# PowerBoard.net
KiCad netlist of a schematic drawn in Altium Designer
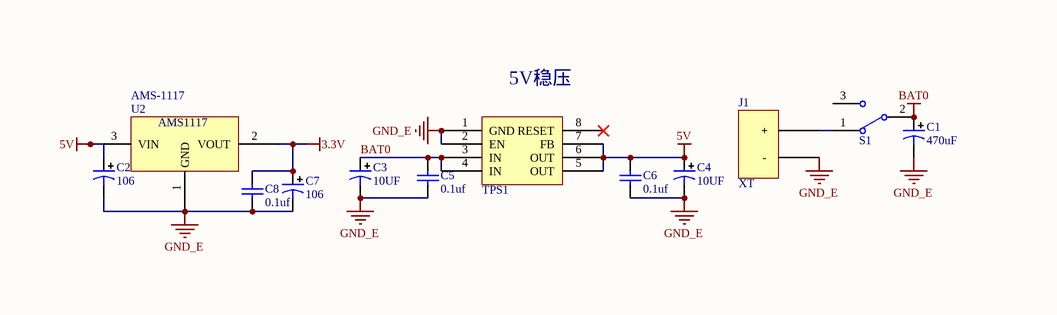
[diagram p0: PowerBoard.SchDoc, top left]
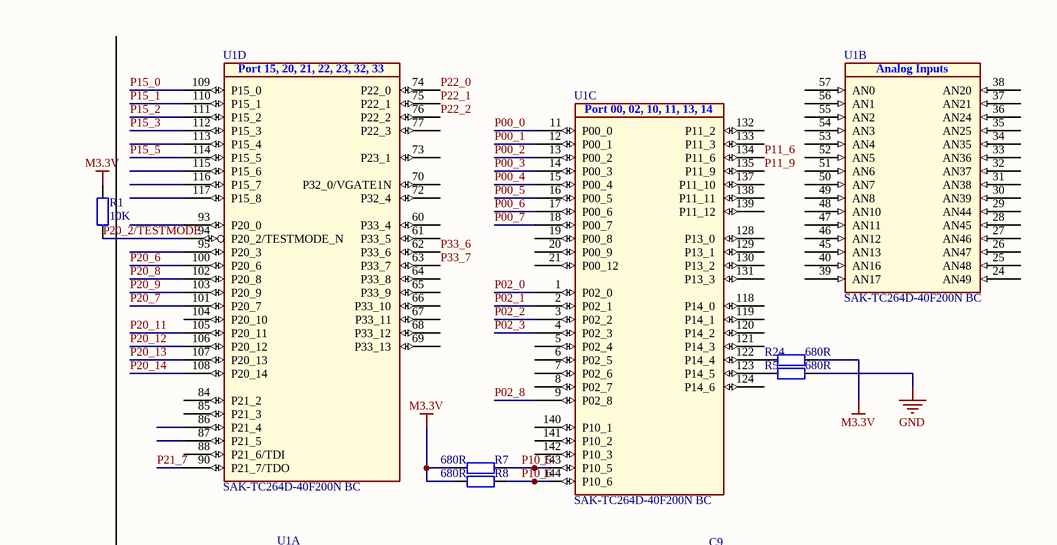
[diagram p1: PowerBoard.SchDoc, top right]
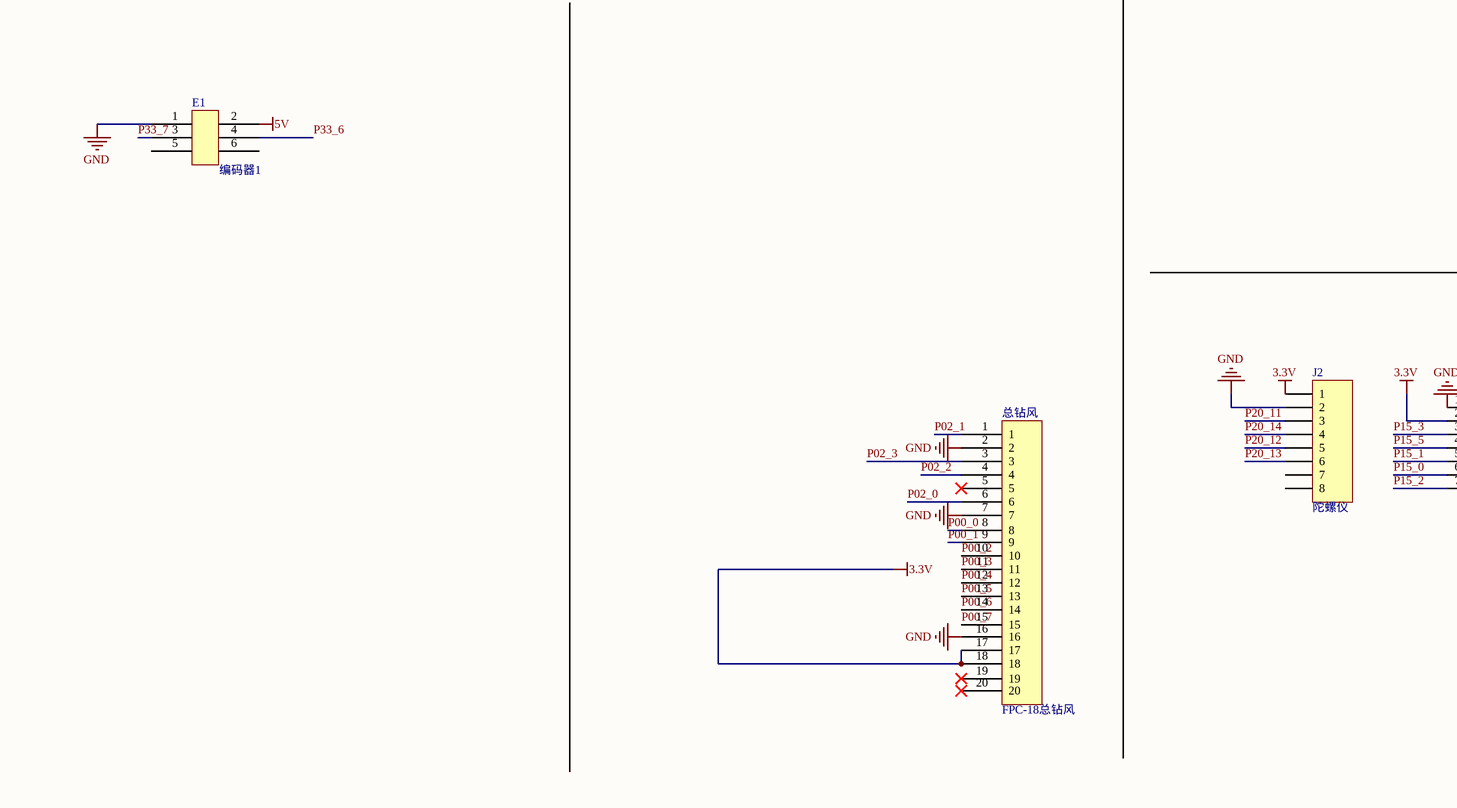
[diagram p2: PowerBoard.SchDoc, bottom left]
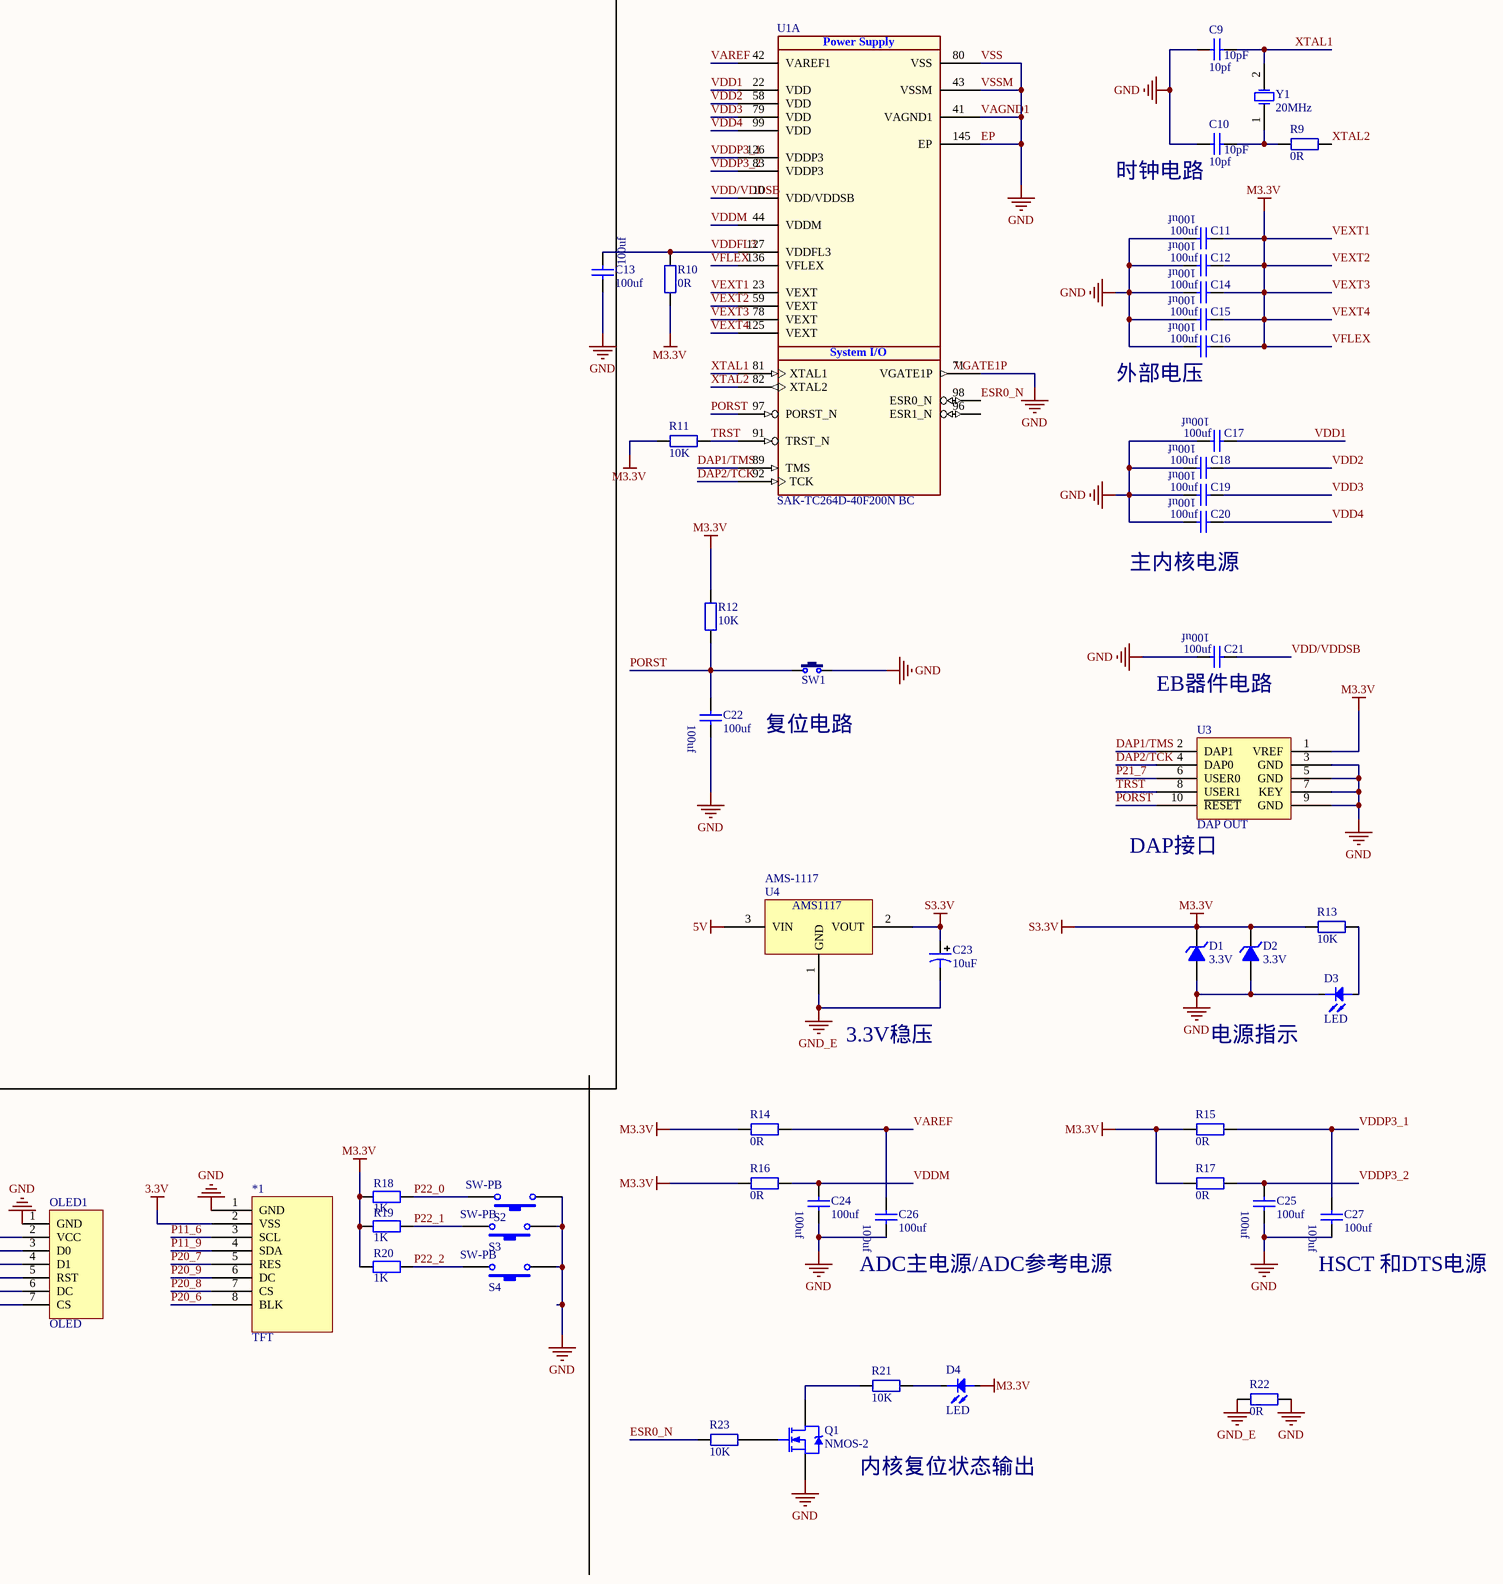
[diagram p3: PowerBoard.SchDoc, bottom right]

(export (version "E")
  (design (tool "Eeschema 10.0.6"))
  (components
    (comp (ref "*1") (value "TFT") (footprint "1.8TFT彩屏") (libsource (lib "PowerBoard") (part "TFT")))
    (comp (ref "C1")
      (value "470uF")
      (footprint "CM E(8*10.2)")
      (description "Capacitor")
      (fields (field (name "Comment") "470uf") (field (name "PUBLISHER") "Altium Limited"))
      (libsource (lib "PowerBoard") (part "Cap2"))
    )
    (comp (ref "C2")
      (value "106")
      (footprint "1206")
      (description "Capacitor")
      (fields (field (name "Comment") "10uf") (field (name "PUBLISHER") "Altium Limited"))
      (libsource (lib "主板常用元器件") (part "Cap2"))
    )
    (comp (ref "C3")
      (value "10UF")
      (footprint "1206")
      (description "Capacitor")
      (fields (field (name "Comment") "10uf") (field (name "PUBLISHER") "Altium Limited"))
      (libsource (lib "主板常用元器件") (part "Cap2"))
    )
    (comp (ref "C4")
      (value "10UF")
      (footprint "1206")
      (description "Capacitor")
      (fields (field (name "Comment") "10uf") (field (name "PUBLISHER") "Altium Limited"))
      (libsource (lib "主板常用元器件") (part "Cap2"))
    )
    (comp (ref "C5")
      (value "0.1uf")
      (footprint "0805C")
      (description "Capacitor")
      (fields (field (name "PUBLISHER") "Altium Limited"))
      (libsource (lib "PowerBoard") (part "Cap1"))
    )
    (comp (ref "C6")
      (value "0.1uf")
      (footprint "0805C")
      (description "Capacitor")
      (fields (field (name "PUBLISHER") "Altium Limited"))
      (libsource (lib "PowerBoard") (part "Cap1"))
    )
    (comp (ref "C7")
      (value "106")
      (footprint "1206")
      (description "Capacitor")
      (fields (field (name "Comment") "10uf") (field (name "PUBLISHER") "Altium Limited"))
      (libsource (lib "主板常用元器件") (part "Cap2"))
    )
    (comp (ref "C8")
      (value "0.1uf")
      (footprint "0805C")
      (description "Capacitor")
      (fields (field (name "PUBLISHER") "Altium Limited"))
      (libsource (lib "PowerBoard") (part "Cap1"))
    )
    (comp (ref "C9")
      (value "10pf")
      (footprint "0805C")
      (description "Capacitor")
      (fields (field (name "PUBLISHER") "Altium Limited"))
      (libsource (lib "PowerBoard") (part "Cap_1"))
    )
    (comp (ref "C10")
      (value "10pf")
      (footprint "0805C")
      (description "Capacitor")
      (fields (field (name "PUBLISHER") "Altium Limited"))
      (libsource (lib "PowerBoard") (part "Cap_1"))
    )
    (comp (ref "C11")
      (value "100uf")
      (footprint "0805C")
      (description "Capacitor")
      (fields (field (name "PUBLISHER") "Altium Limited"))
      (libsource (lib "PowerBoard") (part "Cap"))
    )
    (comp (ref "C12")
      (value "100uf")
      (footprint "0805C")
      (description "Capacitor")
      (fields (field (name "PUBLISHER") "Altium Limited"))
      (libsource (lib "PowerBoard") (part "Cap"))
    )
    (comp (ref "C13")
      (value "100uf")
      (footprint "0805C")
      (description "Capacitor")
      (fields (field (name "PUBLISHER") "Altium Limited"))
      (libsource (lib "PowerBoard") (part "Cap"))
    )
    (comp (ref "C14")
      (value "100uf")
      (footprint "0805C")
      (description "Capacitor")
      (fields (field (name "PUBLISHER") "Altium Limited"))
      (libsource (lib "PowerBoard") (part "Cap"))
    )
    (comp (ref "C15")
      (value "100uf")
      (footprint "0805C")
      (description "Capacitor")
      (fields (field (name "PUBLISHER") "Altium Limited"))
      (libsource (lib "PowerBoard") (part "Cap"))
    )
    (comp (ref "C16")
      (value "100uf")
      (footprint "0805C")
      (description "Capacitor")
      (fields (field (name "PUBLISHER") "Altium Limited"))
      (libsource (lib "PowerBoard") (part "Cap"))
    )
    (comp (ref "C17")
      (value "100uf")
      (footprint "0805C")
      (description "Capacitor")
      (fields (field (name "PUBLISHER") "Altium Limited"))
      (libsource (lib "PowerBoard") (part "Cap"))
    )
    (comp (ref "C18")
      (value "100uf")
      (footprint "0805C")
      (description "Capacitor")
      (fields (field (name "PUBLISHER") "Altium Limited"))
      (libsource (lib "PowerBoard") (part "Cap"))
    )
    (comp (ref "C19")
      (value "100uf")
      (footprint "0805C")
      (description "Capacitor")
      (fields (field (name "PUBLISHER") "Altium Limited"))
      (libsource (lib "PowerBoard") (part "Cap"))
    )
    (comp (ref "C20")
      (value "100uf")
      (footprint "0805C")
      (description "Capacitor")
      (fields (field (name "PUBLISHER") "Altium Limited"))
      (libsource (lib "PowerBoard") (part "Cap"))
    )
    (comp (ref "C21")
      (value "100uf")
      (footprint "0805C")
      (description "Capacitor")
      (fields (field (name "PUBLISHER") "Altium Limited"))
      (libsource (lib "PowerBoard") (part "Cap"))
    )
    (comp (ref "C22")
      (value "100uf")
      (footprint "0805C")
      (description "Capacitor")
      (fields (field (name "PUBLISHER") "Altium Limited"))
      (libsource (lib "PowerBoard") (part "Cap"))
    )
    (comp (ref "C23")
      (value "10uF")
      (footprint "CM E(8*10.2)")
      (description "Capacitor")
      (fields (field (name "Comment") "10uf") (field (name "PUBLISHER") "Altium Limited"))
      (libsource (lib "PowerBoard") (part "Cap2_1"))
    )
    (comp (ref "C24")
      (value "100uf")
      (footprint "0805C")
      (description "Capacitor")
      (fields (field (name "PUBLISHER") "Altium Limited"))
      (libsource (lib "PowerBoard") (part "Cap"))
    )
    (comp (ref "C25")
      (value "100uf")
      (footprint "0805C")
      (description "Capacitor")
      (fields (field (name "PUBLISHER") "Altium Limited"))
      (libsource (lib "PowerBoard") (part "Cap"))
    )
    (comp (ref "C26")
      (value "100uf")
      (footprint "0805C")
      (description "Capacitor")
      (fields (field (name "PUBLISHER") "Altium Limited"))
      (libsource (lib "PowerBoard") (part "Cap"))
    )
    (comp (ref "C27")
      (value "100uf")
      (footprint "0805C")
      (description "Capacitor")
      (fields (field (name "PUBLISHER") "Altium Limited"))
      (libsource (lib "PowerBoard") (part "Cap"))
    )
    (comp (ref "D1")
      (value "3.3V")
      (footprint "DO-35")
      (fields (field (name "版权归属") "源创客"))
      (libsource (lib "PowerBoard") (part "DIODE"))
    )
    (comp (ref "D2")
      (value "3.3V")
      (footprint "DO-35")
      (fields (field (name "版权归属") "源创客"))
      (libsource (lib "PowerBoard") (part "DIODE"))
    )
    (comp (ref "D3") (value "LED") (footprint "0805LED") (libsource (lib "PowerBoard") (part "LED")))
    (comp (ref "D4") (value "LED") (footprint "0805LED") (libsource (lib "PowerBoard") (part "LED")))
    (comp (ref "E1") (value "编码器1") (footprint "IDC-6") (libsource (lib "主板常用元器件") (part "DIP6")))
    (comp (ref "J1") (value "XT") (footprint "XT60") (libsource (lib "PowerBoard") (part "XT")))
    (comp (ref "J2")
      (value "陀螺仪")
      (footprint "HDR1X8")
      (description "Header, 8-Pin")
      (fields (field (name "PUBLISHER") "Altium Limited"))
      (libsource (lib "4.5   - 接插件-脚距2.54") (part "Header 8"))
    )
    (comp (ref "OLED1")
      (value "OLED")
      (footprint "SIP7")
      (fields (field (name "版权归属") "源创客"))
      (libsource (lib "PowerBoard") (part "OLED 1.3-12864_7pin"))
    )
    (comp (ref "Q1")
      (value "NMOS-2")
      (footprint "SOT23-3")
      (description "N-Channel Power MOSFET")
      (fields (field (name "PUBLISHER") "Altium Limited"))
      (libsource (lib "Miscellaneous Devices") (part "NMOS-2"))
    )
    (comp (ref "R1") (value "10K") (footprint "0805R") (libsource (lib "PowerBoard") (part "RES_3")))
    (comp (ref "R5") (value "680R") (footprint "0805R") (libsource (lib "PowerBoard") (part "RES")))
    (comp (ref "R7") (value "680R") (footprint "0805R") (libsource (lib "PowerBoard") (part "RES")))
    (comp (ref "R8") (value "680R") (footprint "0805R") (libsource (lib "PowerBoard") (part "RES")))
    (comp (ref "R9") (value "0R") (footprint "0805R") (libsource (lib "PowerBoard") (part "RES_2")))
    (comp (ref "R10") (value "0R") (footprint "0805R") (libsource (lib "PowerBoard") (part "RES_2")))
    (comp (ref "R11") (value "10K") (footprint "0805R") (libsource (lib "PowerBoard") (part "RES_3")))
    (comp (ref "R12") (value "10K") (footprint "0805R") (libsource (lib "PowerBoard") (part "RES_3")))
    (comp (ref "R13") (value "10K") (footprint "0805R") (libsource (lib "PowerBoard") (part "RES_3")))
    (comp (ref "R14") (value "0R") (footprint "0805R") (libsource (lib "PowerBoard") (part "RES_2")))
    (comp (ref "R15") (value "0R") (footprint "0805R") (libsource (lib "PowerBoard") (part "RES_2")))
    (comp (ref "R16") (value "0R") (footprint "0805R") (libsource (lib "PowerBoard") (part "RES_2")))
    (comp (ref "R17") (value "0R") (footprint "0805R") (libsource (lib "PowerBoard") (part "RES_2")))
    (comp (ref "R18")
      (value "1K")
      (footprint "0805R")
      (description "Resistor")
      (fields (field (name "Comment") "Res2") (field (name "PUBLISHER") "Altium Limited"))
      (libsource (lib "主板常用元器件") (part "Res2"))
    )
    (comp (ref "R19")
      (value "1K")
      (footprint "0805R")
      (description "Resistor")
      (fields (field (name "Comment") "Res2") (field (name "PUBLISHER") "Altium Limited"))
      (libsource (lib "主板常用元器件") (part "Res2"))
    )
    (comp (ref "R20")
      (value "1K")
      (footprint "0805R")
      (description "Resistor")
      (fields (field (name "Comment") "Res2") (field (name "PUBLISHER") "Altium Limited"))
      (libsource (lib "主板常用元器件") (part "Res2"))
    )
    (comp (ref "R21") (value "10K") (footprint "0805R") (libsource (lib "PowerBoard") (part "RES_3")))
    (comp (ref "R22") (value "0R") (footprint "0805R") (libsource (lib "PowerBoard") (part "RES_2")))
    (comp (ref "R23") (value "10K") (footprint "0805R") (libsource (lib "PowerBoard") (part "RES_3")))
    (comp (ref "R24") (value "680R") (footprint "0805R") (libsource (lib "PowerBoard") (part "RES")))
    (comp (ref "S1")
      (value "MTS-10x")
      (footprint "MTS-10x")
      (description "MTS10x系列3脚扭子开关")
      (fields (field (name "版权归属") "源创客"))
      (libsource (lib "PowerBoard") (part "MTS-10x"))
    )
    (comp (ref "S2")
      (value "SW-PB")
      (footprint "TSW SMD-3*6*5")
      (description "Switch")
      (fields (field (name "PUBLISHER") "Altium Limited"))
      (libsource (lib "Miscellaneous Devices") (part "SW-PB"))
    )
    (comp (ref "S3")
      (value "SW-PB")
      (footprint "TSW SMD-3*6*5")
      (description "Switch")
      (fields (field (name "PUBLISHER") "Altium Limited"))
      (libsource (lib "Miscellaneous Devices") (part "SW-PB"))
    )
    (comp (ref "S4")
      (value "SW-PB")
      (footprint "TSW SMD-3*6*5")
      (description "Switch")
      (fields (field (name "PUBLISHER") "Altium Limited"))
      (libsource (lib "Miscellaneous Devices") (part "SW-PB"))
    )
    (comp (ref "SW1")
      (value "6x6x5")
      (footprint "TSW SMD-3*6*5")
      (description "侧按直插6x6轻触开关")
      (fields (field (name "版权归属") "源创客"))
      (libsource (lib "PowerBoard") (part "TSW DIP-6x6_V"))
    )
    (comp (ref "TPS1") (value "TPS7350") (footprint "SO8_L") (libsource (lib "主板常用元器件") (part "TPS7350")))
    (comp (ref "U1")
      (value "SAK-TC264D-40F200N BC")
      (footprint "QFP50P2200X2200X160-145N-1")
      (description "32-Bit Single-Chip Microcontroller BC-Step")
      (fields (field (name "MANUFACTURER") "Infineon Technologies"))
      (libsource (lib "PowerBoard") (part "SAK-TC264D-40F200N BC"))
    )
    (comp (ref "U2")
      (value "AMS-1117")
      (footprint "SOT223-AMS1117")
      (description "1A low dropout viltage regulator")
      (libsource (lib "PowerBoard") (part "AMS-1117"))
    )
    (comp (ref "U3") (value "DAP OUT") (footprint "IDC10") (libsource (lib "PowerBoard") (part "DAP OUT")))
    (comp (ref "U4")
      (value "AMS-1117")
      (footprint "SOT223-AMS1117")
      (description "1A low dropout viltage regulator")
      (libsource (lib "PowerBoard") (part "AMS-1117"))
    )
    (comp (ref "Y1")
      (value "20MHz")
      (footprint "OSC 5032-2P")
      (description "Crystal Oscillator")
      (fields (field (name "PUBLISHER") "Altium Limited"))
      (libsource (lib "PowerBoard") (part "XTAL"))
    )
    (comp (ref "总钻风")
      (value "FPC-18总钻风")
      (footprint "FH12-18S-0.5SH")
      (libsource (lib "主板常用元器件") (part "FPC-18总钻风"))
    )
  )
  (nets
    (net (code "1") (name "/DAP1{slash}TMS") (class "Default")
      (node (ref "U1") (pin "89") (pinfunction "TMS_89") (pintype "input"))
      (node (ref "U3") (pin "2") (pinfunction "DAP1_2") (pintype "passive"))
    )
    (net (code "2") (name "/DAP2{slash}TCK") (class "Default")
      (node (ref "U1") (pin "92") (pinfunction "TCK_92") (pintype "input"))
      (node (ref "U3") (pin "4") (pinfunction "DAP0_4") (pintype "passive"))
    )
    (net (code "3") (name "/ESR0_N") (class "Default")
      (node (ref "R23") (pin "2") (pinfunction "2_2") (pintype "passive"))
      (node (ref "U1") (pin "98") (pinfunction "ESR0_N_98") (pintype "bidirectional"))
    )
    (net (code "4") (name "/P00_0") (class "Default")
      (node (ref "U1") (pin "11") (pinfunction "P00_0_11") (pintype "bidirectional"))
      (node (ref "总钻风") (pin "8") (pinfunction "8_8") (pintype "passive"))
    )
    (net (code "5") (name "/P00_1") (class "Default")
      (node (ref "U1") (pin "12") (pinfunction "P00_1_12") (pintype "bidirectional"))
      (node (ref "总钻风") (pin "9") (pinfunction "9_9") (pintype "passive"))
    )
    (net (code "6") (name "/P00_2") (class "Default")
      (node (ref "U1") (pin "13") (pinfunction "P00_2_13") (pintype "bidirectional"))
      (node (ref "总钻风") (pin "10") (pinfunction "10_10") (pintype "passive"))
    )
    (net (code "7") (name "/P00_3") (class "Default")
      (node (ref "U1") (pin "14") (pinfunction "P00_3_14") (pintype "bidirectional"))
      (node (ref "总钻风") (pin "11") (pinfunction "11_11") (pintype "passive"))
    )
    (net (code "8") (name "/P00_4") (class "Default")
      (node (ref "U1") (pin "15") (pinfunction "P00_4_15") (pintype "bidirectional"))
      (node (ref "总钻风") (pin "12") (pinfunction "12_12") (pintype "passive"))
    )
    (net (code "9") (name "/P00_5") (class "Default")
      (node (ref "U1") (pin "16") (pinfunction "P00_5_16") (pintype "bidirectional"))
      (node (ref "总钻风") (pin "13") (pinfunction "13_13") (pintype "passive"))
    )
    (net (code "10") (name "/P00_6") (class "Default")
      (node (ref "U1") (pin "17") (pinfunction "P00_6_17") (pintype "bidirectional"))
      (node (ref "总钻风") (pin "14") (pinfunction "14_14") (pintype "passive"))
    )
    (net (code "11") (name "/P00_7") (class "Default")
      (node (ref "U1") (pin "18") (pinfunction "P00_7_18") (pintype "bidirectional"))
      (node (ref "总钻风") (pin "15") (pinfunction "15_15") (pintype "passive"))
    )
    (net (code "12") (name "/P02_0") (class "Default")
      (node (ref "U1") (pin "1") (pinfunction "P02_0_1") (pintype "bidirectional"))
      (node (ref "总钻风") (pin "6") (pinfunction "6_6") (pintype "passive"))
    )
    (net (code "13") (name "/P02_1") (class "Default")
      (node (ref "U1") (pin "2") (pinfunction "P02_1_2") (pintype "bidirectional"))
      (node (ref "总钻风") (pin "1") (pinfunction "1_1") (pintype "passive"))
    )
    (net (code "14") (name "/P02_2") (class "Default")
      (node (ref "U1") (pin "3") (pinfunction "P02_2_3") (pintype "bidirectional"))
      (node (ref "总钻风") (pin "4") (pinfunction "4_4") (pintype "passive"))
    )
    (net (code "15") (name "/P02_3") (class "Default")
      (node (ref "U1") (pin "4") (pinfunction "P02_3_4") (pintype "bidirectional"))
      (node (ref "总钻风") (pin "3") (pinfunction "3_3") (pintype "passive"))
    )
    (net (code "16") (name "/P02_8") (class "Default")
      (node (ref "U1") (pin "9") (pinfunction "P02_8_9") (pintype "bidirectional"))
    )
    (net (code "17") (name "/P10_5") (class "Default")
      (node (ref "R7") (pin "2") (pinfunction "2_2") (pintype "passive"))
      (node (ref "U1") (pin "143") (pinfunction "P10_5_143") (pintype "bidirectional"))
    )
    (net (code "18") (name "/P10_6") (class "Default")
      (node (ref "R8") (pin "2") (pinfunction "2_2") (pintype "passive"))
      (node (ref "U1") (pin "144") (pinfunction "P10_6_144") (pintype "bidirectional"))
    )
    (net (code "19") (name "/P11_6") (class "Default")
      (node (ref "*1") (pin "3") (pinfunction "SCL_3") (pintype "passive"))
      (node (ref "U1") (pin "134") (pinfunction "P11_6_134") (pintype "bidirectional"))
    )
    (net (code "20") (name "/P11_9") (class "Default")
      (node (ref "*1") (pin "4") (pinfunction "SDA_4") (pintype "passive"))
      (node (ref "U1") (pin "135") (pinfunction "P11_9_135") (pintype "bidirectional"))
    )
    (net (code "21") (name "/P15_0") (class "Default")
      (node (ref "OLED1") (pin "6") (pinfunction "DC_6") (pintype "passive"))
      (node (ref "U1") (pin "109") (pinfunction "P15_0_109") (pintype "bidirectional"))
    )
    (net (code "22") (name "/P15_1") (class "Default")
      (node (ref "OLED1") (pin "5") (pinfunction "RST_5") (pintype "passive"))
      (node (ref "U1") (pin "110") (pinfunction "P15_1_110") (pintype "bidirectional"))
    )
    (net (code "23") (name "/P15_2") (class "Default")
      (node (ref "OLED1") (pin "7") (pinfunction "CS_7") (pintype "passive"))
      (node (ref "U1") (pin "111") (pinfunction "P15_2_111") (pintype "bidirectional"))
    )
    (net (code "24") (name "/P15_3") (class "Default")
      (node (ref "OLED1") (pin "3") (pinfunction "D0_3") (pintype "passive"))
      (node (ref "U1") (pin "112") (pinfunction "P15_3_112") (pintype "bidirectional"))
    )
    (net (code "25") (name "/P15_5") (class "Default")
      (node (ref "OLED1") (pin "4") (pinfunction "D1_4") (pintype "passive"))
      (node (ref "U1") (pin "114") (pinfunction "P15_5_114") (pintype "bidirectional"))
    )
    (net (code "26") (name "/P20_2{slash}TESTMODE") (class "Default")
      (node (ref "R1") (pin "1") (pinfunction "1_1") (pintype "passive"))
      (node (ref "U1") (pin "94") (pinfunction "P20_2/TESTMODE_N_94") (pintype "bidirectional"))
    )
    (net (code "27") (name "/P20_6") (class "Default")
      (node (ref "*1") (pin "8") (pinfunction "BLK_8") (pintype "passive"))
      (node (ref "U1") (pin "100") (pinfunction "P20_6_100") (pintype "bidirectional"))
    )
    (net (code "28") (name "/P20_7") (class "Default")
      (node (ref "*1") (pin "5") (pinfunction "RES_5") (pintype "passive"))
      (node (ref "U1") (pin "101") (pinfunction "P20_7_101") (pintype "bidirectional"))
    )
    (net (code "29") (name "/P20_8") (class "Default")
      (node (ref "*1") (pin "7") (pinfunction "CS_7") (pintype "passive"))
      (node (ref "U1") (pin "102") (pinfunction "P20_8_102") (pintype "bidirectional"))
    )
    (net (code "30") (name "/P20_9") (class "Default")
      (node (ref "*1") (pin "6") (pinfunction "DC_6") (pintype "passive"))
      (node (ref "U1") (pin "103") (pinfunction "P20_9_103") (pintype "bidirectional"))
    )
    (net (code "31") (name "/P20_11") (class "Default")
      (node (ref "J2") (pin "3") (pinfunction "3_3") (pintype "passive"))
      (node (ref "U1") (pin "105") (pinfunction "P20_11_105") (pintype "bidirectional"))
    )
    (net (code "32") (name "/P20_12") (class "Default")
      (node (ref "J2") (pin "5") (pinfunction "5_5") (pintype "passive"))
      (node (ref "U1") (pin "106") (pinfunction "P20_12_106") (pintype "bidirectional"))
    )
    (net (code "33") (name "/P20_13") (class "Default")
      (node (ref "J2") (pin "6") (pinfunction "6_6") (pintype "passive"))
      (node (ref "U1") (pin "107") (pinfunction "P20_13_107") (pintype "bidirectional"))
    )
    (net (code "34") (name "/P20_14") (class "Default")
      (node (ref "J2") (pin "4") (pinfunction "4_4") (pintype "passive"))
      (node (ref "U1") (pin "108") (pinfunction "P20_14_108") (pintype "bidirectional"))
    )
    (net (code "35") (name "/P21_7") (class "Default")
      (node (ref "U1") (pin "90") (pinfunction "P21_7/TDO_90") (pintype "bidirectional"))
      (node (ref "U3") (pin "6") (pinfunction "USER0_6") (pintype "passive"))
    )
    (net (code "36") (name "/P22_0") (class "Default")
      (node (ref "R18") (pin "2") (pinfunction "2_2") (pintype "passive"))
      (node (ref "S2") (pin "2") (pinfunction "2_2") (pintype "passive"))
      (node (ref "U1") (pin "74") (pinfunction "P22_0_74") (pintype "bidirectional"))
    )
    (net (code "37") (name "/P22_1") (class "Default")
      (node (ref "R19") (pin "2") (pinfunction "2_2") (pintype "passive"))
      (node (ref "S3") (pin "2") (pinfunction "2_2") (pintype "passive"))
      (node (ref "U1") (pin "75") (pinfunction "P22_1_75") (pintype "bidirectional"))
    )
    (net (code "38") (name "/P22_2") (class "Default")
      (node (ref "R20") (pin "2") (pinfunction "2_2") (pintype "passive"))
      (node (ref "S4") (pin "2") (pinfunction "2_2") (pintype "passive"))
      (node (ref "U1") (pin "76") (pinfunction "P22_2_76") (pintype "bidirectional"))
    )
    (net (code "39") (name "/P33_6") (class "Default")
      (node (ref "E1") (pin "4") (pinfunction "4_4") (pintype "passive"))
      (node (ref "U1") (pin "62") (pinfunction "P33_6_62") (pintype "bidirectional"))
    )
    (net (code "40") (name "/P33_7") (class "Default")
      (node (ref "E1") (pin "3") (pinfunction "3_3") (pintype "passive"))
      (node (ref "U1") (pin "63") (pinfunction "P33_7_63") (pintype "bidirectional"))
    )
    (net (code "41") (name "/PORST") (class "Default")
      (node (ref "C22") (pin "1") (pinfunction "1_1") (pintype "passive"))
      (node (ref "R12") (pin "1") (pinfunction "1_1") (pintype "passive"))
      (node (ref "SW1") (pin "1") (pinfunction "1_1") (pintype "passive"))
      (node (ref "U1") (pin "97") (pinfunction "PORST_N_97") (pintype "input"))
      (node (ref "U3") (pin "10") (pinfunction "~{RESET}_10") (pintype "passive"))
    )
    (net (code "42") (name "/TRST") (class "Default")
      (node (ref "R11") (pin "1") (pinfunction "1_1") (pintype "passive"))
      (node (ref "U1") (pin "91") (pinfunction "TRST_N_91") (pintype "input"))
      (node (ref "U3") (pin "8") (pinfunction "USER1_8") (pintype "passive"))
    )
    (net (code "43") (name "/VAREF") (class "Default")
      (node (ref "C26") (pin "1") (pinfunction "1_1") (pintype "passive"))
      (node (ref "R14") (pin "2") (pinfunction "2_2") (pintype "passive"))
      (node (ref "U1") (pin "42") (pinfunction "VAREF1_42") (pintype "power_in"))
    )
    (net (code "44") (name "/VDD1") (class "Default")
      (node (ref "C17") (pin "1") (pinfunction "1_1") (pintype "passive"))
      (node (ref "U1") (pin "22") (pinfunction "VDD_22") (pintype "power_in"))
    )
    (net (code "45") (name "/VDD2") (class "Default")
      (node (ref "C18") (pin "1") (pinfunction "1_1") (pintype "passive"))
      (node (ref "U1") (pin "58") (pinfunction "VDD_58") (pintype "power_in"))
    )
    (net (code "46") (name "/VDD3") (class "Default")
      (node (ref "C19") (pin "1") (pinfunction "1_1") (pintype "passive"))
      (node (ref "U1") (pin "79") (pinfunction "VDD_79") (pintype "power_in"))
    )
    (net (code "47") (name "/VDD4") (class "Default")
      (node (ref "C20") (pin "1") (pinfunction "1_1") (pintype "passive"))
      (node (ref "U1") (pin "99") (pinfunction "VDD_99") (pintype "power_in"))
    )
    (net (code "48") (name "/VDDFL3") (class "Default")
      (node (ref "C13") (pin "2") (pinfunction "2_2") (pintype "passive"))
      (node (ref "R10") (pin "2") (pinfunction "2_2") (pintype "passive"))
      (node (ref "U1") (pin "127") (pinfunction "VDDFL3_127") (pintype "power_in"))
    )
    (net (code "49") (name "/VDDM") (class "Default")
      (node (ref "C24") (pin "1") (pinfunction "1_1") (pintype "passive"))
      (node (ref "R16") (pin "2") (pinfunction "2_2") (pintype "passive"))
      (node (ref "U1") (pin "44") (pinfunction "VDDM_44") (pintype "power_in"))
    )
    (net (code "50") (name "/VDDP3_1") (class "Default")
      (node (ref "C27") (pin "1") (pinfunction "1_1") (pintype "passive"))
      (node (ref "R15") (pin "2") (pinfunction "2_2") (pintype "passive"))
      (node (ref "U1") (pin "126") (pinfunction "VDDP3_126") (pintype "power_in"))
    )
    (net (code "51") (name "/VDDP3_2") (class "Default")
      (node (ref "C25") (pin "1") (pinfunction "1_1") (pintype "passive"))
      (node (ref "R17") (pin "2") (pinfunction "2_2") (pintype "passive"))
      (node (ref "U1") (pin "83") (pinfunction "VDDP3_83") (pintype "power_in"))
    )
    (net (code "52") (name "/VDD{slash}VDDSB") (class "Default")
      (node (ref "C21") (pin "1") (pinfunction "1_1") (pintype "passive"))
      (node (ref "U1") (pin "10") (pinfunction "VDD/VDDSB_10") (pintype "power_in"))
    )
    (net (code "54") (name "/XTAL1") (class "Default")
      (node (ref "C9") (pin "2") (pinfunction "2_2") (pintype "passive"))
      (node (ref "U1") (pin "81") (pinfunction "XTAL1_81") (pintype "input"))
      (node (ref "Y1") (pin "2") (pinfunction "OSC2_2") (pintype "passive"))
    )
    (net (code "55") (name "/XTAL2") (class "Default")
      (node (ref "R9") (pin "2") (pinfunction "2_2") (pintype "passive"))
      (node (ref "U1") (pin "82") (pinfunction "XTAL2_82") (pintype "output"))
    )
    (net (code "56") (name "3.3V") (class "Default")
      (node (ref "*1") (pin "2") (pinfunction "VSS_2") (pintype "passive"))
      (node (ref "C7") (pin "1") (pinfunction "1_1") (pintype "passive"))
      (node (ref "C8") (pin "1") (pinfunction "1_1") (pintype "passive"))
      (node (ref "J2") (pin "1") (pinfunction "1_1") (pintype "passive"))
      (node (ref "OLED1") (pin "2") (pinfunction "VCC_2") (pintype "passive"))
      (node (ref "U2") (pin "2") (pinfunction "VOUT_2") (pintype "passive"))
      (node (ref "总钻风") (pin "17") (pinfunction "17_17") (pintype "passive"))
      (node (ref "总钻风") (pin "18") (pinfunction "18_18") (pintype "passive"))
    )
    (net (code "57") (name "5V") (class "Default")
      (node (ref "C2") (pin "1") (pinfunction "1_1") (pintype "passive"))
      (node (ref "C4") (pin "1") (pinfunction "1_1") (pintype "passive"))
      (node (ref "C6") (pin "1") (pinfunction "1_1") (pintype "passive"))
      (node (ref "E1") (pin "2") (pinfunction "2_2") (pintype "passive"))
      (node (ref "TPS1") (pin "5") (pinfunction "OUT_5") (pintype "passive"))
      (node (ref "TPS1") (pin "6") (pinfunction "OUT_6") (pintype "passive"))
      (node (ref "TPS1") (pin "7") (pinfunction "FB_7") (pintype "passive"))
      (node (ref "U2") (pin "3") (pinfunction "VIN_3") (pintype "passive"))
      (node (ref "U4") (pin "3") (pinfunction "VIN_3") (pintype "passive"))
    )
    (net (code "58") (name "BAT0") (class "Default")
      (node (ref "C1") (pin "1") (pinfunction "1_1") (pintype "passive"))
      (node (ref "C3") (pin "1") (pinfunction "1_1") (pintype "passive"))
      (node (ref "C5") (pin "1") (pinfunction "1_1") (pintype "passive"))
      (node (ref "S1") (pin "2") (pinfunction "2_2") (pintype "passive"))
      (node (ref "TPS1") (pin "3") (pinfunction "IN_3") (pintype "passive"))
      (node (ref "TPS1") (pin "4") (pinfunction "IN_4") (pintype "passive"))
    )
    (net (code "59") (name "GND") (class "Default")
      (node (ref "*1") (pin "1") (pinfunction "GND_1") (pintype "passive"))
      (node (ref "C10") (pin "1") (pinfunction "1_1") (pintype "passive"))
      (node (ref "C11") (pin "2") (pinfunction "2_2") (pintype "passive"))
      (node (ref "C12") (pin "2") (pinfunction "2_2") (pintype "passive"))
      (node (ref "C13") (pin "1") (pinfunction "1_1") (pintype "passive"))
      (node (ref "C14") (pin "2") (pinfunction "2_2") (pintype "passive"))
      (node (ref "C15") (pin "2") (pinfunction "2_2") (pintype "passive"))
      (node (ref "C16") (pin "2") (pinfunction "2_2") (pintype "passive"))
      (node (ref "C17") (pin "2") (pinfunction "2_2") (pintype "passive"))
      (node (ref "C18") (pin "2") (pinfunction "2_2") (pintype "passive"))
      (node (ref "C19") (pin "2") (pinfunction "2_2") (pintype "passive"))
      (node (ref "C20") (pin "2") (pinfunction "2_2") (pintype "passive"))
      (node (ref "C21") (pin "2") (pinfunction "2_2") (pintype "passive"))
      (node (ref "C22") (pin "2") (pinfunction "2_2") (pintype "passive"))
      (node (ref "C24") (pin "2") (pinfunction "2_2") (pintype "passive"))
      (node (ref "C25") (pin "2") (pinfunction "2_2") (pintype "passive"))
      (node (ref "C26") (pin "2") (pinfunction "2_2") (pintype "passive"))
      (node (ref "C27") (pin "2") (pinfunction "2_2") (pintype "passive"))
      (node (ref "C9") (pin "1") (pinfunction "1_1") (pintype "passive"))
      (node (ref "D1") (pin "1") (pinfunction "A_1") (pintype "passive"))
      (node (ref "D2") (pin "1") (pinfunction "A_1") (pintype "passive"))
      (node (ref "D3") (pin "2") (pintype "passive"))
      (node (ref "E1") (pin "1") (pinfunction "1_1") (pintype "passive"))
      (node (ref "J2") (pin "2") (pinfunction "2_2") (pintype "passive"))
      (node (ref "OLED1") (pin "1") (pinfunction "GND_1") (pintype "passive"))
      (node (ref "Q1") (pin "3") (pinfunction "S_3") (pintype "passive"))
      (node (ref "R22") (pin "2") (pinfunction "2_2") (pintype "passive"))
      (node (ref "R5") (pin "2") (pinfunction "2_2") (pintype "passive"))
      (node (ref "S2") (pin "1") (pinfunction "1_1") (pintype "passive"))
      (node (ref "S3") (pin "1") (pinfunction "1_1") (pintype "passive"))
      (node (ref "S4") (pin "1") (pinfunction "1_1") (pintype "passive"))
      (node (ref "SW1") (pin "2") (pinfunction "2_2") (pintype "passive"))
      (node (ref "U1") (pin "145") (pinfunction "EP_145") (pintype "power_in"))
      (node (ref "U1") (pin "41") (pinfunction "VAGND1_41") (pintype "power_in"))
      (node (ref "U1") (pin "43") (pinfunction "VSSM_43") (pintype "power_in"))
      (node (ref "U1") (pin "71") (pinfunction "VGATE1P_71") (pintype "output"))
      (node (ref "U1") (pin "80") (pinfunction "VSS_80") (pintype "power_in"))
      (node (ref "U3") (pin "3") (pinfunction "GND_3") (pintype "passive"))
      (node (ref "U3") (pin "5") (pinfunction "GND_5") (pintype "passive"))
      (node (ref "U3") (pin "7") (pinfunction "KEY_7") (pintype "passive"))
      (node (ref "U3") (pin "9") (pinfunction "GND_9") (pintype "passive"))
      (node (ref "总钻风") (pin "16") (pinfunction "16_16") (pintype "passive"))
      (node (ref "总钻风") (pin "2") (pinfunction "2_2") (pintype "passive"))
      (node (ref "总钻风") (pin "7") (pinfunction "7_7") (pintype "passive"))
    )
    (net (code "60") (name "GND_E") (class "Default")
      (node (ref "C1") (pin "2") (pinfunction "2_2") (pintype "passive"))
      (node (ref "C2") (pin "2") (pinfunction "2_2") (pintype "passive"))
      (node (ref "C23") (pin "2") (pinfunction "2_2") (pintype "passive"))
      (node (ref "C3") (pin "2") (pinfunction "2_2") (pintype "passive"))
      (node (ref "C4") (pin "2") (pinfunction "2_2") (pintype "passive"))
      (node (ref "C5") (pin "2") (pinfunction "2_2") (pintype "passive"))
      (node (ref "C6") (pin "2") (pinfunction "2_2") (pintype "passive"))
      (node (ref "C7") (pin "2") (pinfunction "2_2") (pintype "passive"))
      (node (ref "C8") (pin "2") (pinfunction "2_2") (pintype "passive"))
      (node (ref "J1") (pin "2") (pinfunction "－_2") (pintype "passive"))
      (node (ref "R22") (pin "1") (pinfunction "1_1") (pintype "passive"))
      (node (ref "TPS1") (pin "1") (pinfunction "GND_1") (pintype "passive"))
      (node (ref "TPS1") (pin "2") (pinfunction "EN_2") (pintype "passive"))
      (node (ref "U2") (pin "1") (pinfunction "GND_1") (pintype "passive"))
      (node (ref "U4") (pin "1") (pinfunction "GND_1") (pintype "passive"))
    )
    (net (code "61") (name "M3.3V") (class "Default")
      (node (ref "C11") (pin "1") (pinfunction "1_1") (pintype "passive"))
      (node (ref "C12") (pin "1") (pinfunction "1_1") (pintype "passive"))
      (node (ref "C14") (pin "1") (pinfunction "1_1") (pintype "passive"))
      (node (ref "C15") (pin "1") (pinfunction "1_1") (pintype "passive"))
      (node (ref "C16") (pin "1") (pinfunction "1_1") (pintype "passive"))
      (node (ref "C23") (pin "1") (pinfunction "1_1") (pintype "passive"))
      (node (ref "D1") (pin "2") (pinfunction "K_2") (pintype "passive"))
      (node (ref "D2") (pin "2") (pinfunction "K_2") (pintype "passive"))
      (node (ref "D4") (pin "1") (pintype "passive"))
      (node (ref "R1") (pin "2") (pinfunction "2_2") (pintype "passive"))
      (node (ref "R10") (pin "1") (pinfunction "1_1") (pintype "passive"))
      (node (ref "R11") (pin "2") (pinfunction "2_2") (pintype "passive"))
      (node (ref "R12") (pin "2") (pinfunction "2_2") (pintype "passive"))
      (node (ref "R13") (pin "2") (pinfunction "2_2") (pintype "passive"))
      (node (ref "R14") (pin "1") (pinfunction "1_1") (pintype "passive"))
      (node (ref "R15") (pin "1") (pinfunction "1_1") (pintype "passive"))
      (node (ref "R16") (pin "1") (pinfunction "1_1") (pintype "passive"))
      (node (ref "R17") (pin "1") (pinfunction "1_1") (pintype "passive"))
      (node (ref "R18") (pin "1") (pinfunction "1_1") (pintype "passive"))
      (node (ref "R19") (pin "1") (pinfunction "1_1") (pintype "passive"))
      (node (ref "R20") (pin "1") (pinfunction "1_1") (pintype "passive"))
      (node (ref "R24") (pin "2") (pinfunction "2_2") (pintype "passive"))
      (node (ref "R7") (pin "1") (pinfunction "1_1") (pintype "passive"))
      (node (ref "R8") (pin "1") (pinfunction "1_1") (pintype "passive"))
      (node (ref "U1") (pin "125") (pinfunction "VEXT_125") (pintype "power_in"))
      (node (ref "U1") (pin "136") (pinfunction "VFLEX_136") (pintype "power_in"))
      (node (ref "U1") (pin "23") (pinfunction "VEXT_23") (pintype "power_in"))
      (node (ref "U1") (pin "59") (pinfunction "VEXT_59") (pintype "power_in"))
      (node (ref "U1") (pin "78") (pinfunction "VEXT_78") (pintype "power_in"))
      (node (ref "U3") (pin "1") (pinfunction "VREF_1") (pintype "passive"))
      (node (ref "U4") (pin "2") (pinfunction "VOUT_2") (pintype "passive"))
    )
    (net (code "62") (name "Net-(D3-Pad1)") (class "Default")
      (node (ref "D3") (pin "1") (pintype "passive"))
      (node (ref "R13") (pin "1") (pinfunction "1_1") (pintype "passive"))
    )
    (net (code "63") (name "Net-(D4-Pad2)") (class "Default")
      (node (ref "D4") (pin "2") (pintype "passive"))
      (node (ref "R21") (pin "1") (pinfunction "1_1") (pintype "passive"))
    )
    (net (code "64") (name "Net-(J1-＋)") (class "Default")
      (node (ref "J1") (pin "1") (pinfunction "＋_1") (pintype "passive"))
      (node (ref "S1") (pin "1") (pinfunction "1_1") (pintype "passive"))
    )
    (net (code "65") (name "Net-(Q1-D)") (class "Default")
      (node (ref "Q1") (pin "2") (pinfunction "D_2") (pintype "passive"))
      (node (ref "R21") (pin "2") (pinfunction "2_2") (pintype "passive"))
    )
    (net (code "66") (name "Net-(Q1-G)") (class "Default")
      (node (ref "Q1") (pin "1") (pinfunction "G_1") (pintype "passive"))
      (node (ref "R23") (pin "1") (pinfunction "1_1") (pintype "passive"))
    )
    (net (code "67") (name "Net-(U1C-P14_4)") (class "Default")
      (node (ref "R24") (pin "1") (pinfunction "1_1") (pintype "passive"))
      (node (ref "U1") (pin "122") (pinfunction "P14_4_122") (pintype "bidirectional"))
    )
    (net (code "68") (name "Net-(U1C-P14_5)") (class "Default")
      (node (ref "R5") (pin "1") (pinfunction "1_1") (pintype "passive"))
      (node (ref "U1") (pin "123") (pinfunction "P14_5_123") (pintype "bidirectional"))
    )
    (net (code "69") (name "Net-(Y1-OSC1)") (class "Default")
      (node (ref "C10") (pin "2") (pinfunction "2_2") (pintype "passive"))
      (node (ref "R9") (pin "1") (pinfunction "1_1") (pintype "passive"))
      (node (ref "Y1") (pin "1") (pinfunction "OSC1_1") (pintype "passive"))
    )
    (net (code "70") (name "unconnected-(E1-Pad5)") (class "Default")
      (node (ref "E1") (pin "5") (pinfunction "5_5") (pintype "passive"))
    )
    (net (code "71") (name "unconnected-(E1-Pad6)") (class "Default")
      (node (ref "E1") (pin "6") (pinfunction "6_6") (pintype "passive"))
    )
    (net (code "72") (name "unconnected-(J2-Pad7)") (class "Default")
      (node (ref "J2") (pin "7") (pinfunction "7_7") (pintype "passive"))
    )
    (net (code "73") (name "unconnected-(J2-Pad8)") (class "Default")
      (node (ref "J2") (pin "8") (pinfunction "8_8") (pintype "passive"))
    )
    (net (code "74") (name "unconnected-(S1-Pad3)") (class "Default")
      (node (ref "S1") (pin "3") (pinfunction "3_3") (pintype "passive"))
    )
    (net (code "75") (name "unconnected-(TPS1-RESET-Pad8)") (class "Default")
      (node (ref "TPS1") (pin "8") (pinfunction "RESET_8") (pintype "passive+no_connect"))
    )
    (net (code "76") (name "unconnected-(U1A-ESR1_N-Pad96)") (class "Default")
      (node (ref "U1") (pin "96") (pinfunction "ESR1_N_96") (pintype "bidirectional"))
    )
    (net (code "77") (name "unconnected-(U1B-AN0-Pad57)") (class "Default")
      (node (ref "U1") (pin "57") (pinfunction "AN0_57") (pintype "input"))
    )
    (net (code "78") (name "unconnected-(U1B-AN1-Pad56)") (class "Default")
      (node (ref "U1") (pin "56") (pinfunction "AN1_56") (pintype "input"))
    )
    (net (code "79") (name "unconnected-(U1B-AN2-Pad55)") (class "Default")
      (node (ref "U1") (pin "55") (pinfunction "AN2_55") (pintype "input"))
    )
    (net (code "80") (name "unconnected-(U1B-AN3-Pad54)") (class "Default")
      (node (ref "U1") (pin "54") (pinfunction "AN3_54") (pintype "input"))
    )
    (net (code "81") (name "unconnected-(U1B-AN4-Pad53)") (class "Default")
      (node (ref "U1") (pin "53") (pinfunction "AN4_53") (pintype "input"))
    )
    (net (code "82") (name "unconnected-(U1B-AN5-Pad52)") (class "Default")
      (node (ref "U1") (pin "52") (pinfunction "AN5_52") (pintype "input"))
    )
    (net (code "83") (name "unconnected-(U1B-AN6-Pad51)") (class "Default")
      (node (ref "U1") (pin "51") (pinfunction "AN6_51") (pintype "input"))
    )
    (net (code "84") (name "unconnected-(U1B-AN7-Pad50)") (class "Default")
      (node (ref "U1") (pin "50") (pinfunction "AN7_50") (pintype "input"))
    )
    (net (code "85") (name "unconnected-(U1B-AN8-Pad49)") (class "Default")
      (node (ref "U1") (pin "49") (pinfunction "AN8_49") (pintype "input"))
    )
    (net (code "86") (name "unconnected-(U1B-AN10-Pad48)") (class "Default")
      (node (ref "U1") (pin "48") (pinfunction "AN10_48") (pintype "input"))
    )
    (net (code "87") (name "unconnected-(U1B-AN11-Pad47)") (class "Default")
      (node (ref "U1") (pin "47") (pinfunction "AN11_47") (pintype "input"))
    )
    (net (code "88") (name "unconnected-(U1B-AN12-Pad46)") (class "Default")
      (node (ref "U1") (pin "46") (pinfunction "AN12_46") (pintype "input"))
    )
    (net (code "89") (name "unconnected-(U1B-AN13-Pad45)") (class "Default")
      (node (ref "U1") (pin "45") (pinfunction "AN13_45") (pintype "input"))
    )
    (net (code "90") (name "unconnected-(U1B-AN16-Pad40)") (class "Default")
      (node (ref "U1") (pin "40") (pinfunction "AN16_40") (pintype "input"))
    )
    (net (code "91") (name "unconnected-(U1B-AN17-Pad39)") (class "Default")
      (node (ref "U1") (pin "39") (pinfunction "AN17_39") (pintype "input"))
    )
    (net (code "92") (name "unconnected-(U1B-AN20-Pad38)") (class "Default")
      (node (ref "U1") (pin "38") (pinfunction "AN20_38") (pintype "input"))
    )
    (net (code "93") (name "unconnected-(U1B-AN21-Pad37)") (class "Default")
      (node (ref "U1") (pin "37") (pinfunction "AN21_37") (pintype "input"))
    )
    (net (code "94") (name "unconnected-(U1B-AN24-Pad36)") (class "Default")
      (node (ref "U1") (pin "36") (pinfunction "AN24_36") (pintype "input"))
    )
    (net (code "95") (name "unconnected-(U1B-AN25-Pad35)") (class "Default")
      (node (ref "U1") (pin "35") (pinfunction "AN25_35") (pintype "input"))
    )
    (net (code "96") (name "unconnected-(U1B-AN35-Pad34)") (class "Default")
      (node (ref "U1") (pin "34") (pinfunction "AN35_34") (pintype "input"))
    )
    (net (code "97") (name "unconnected-(U1B-AN36-Pad33)") (class "Default")
      (node (ref "U1") (pin "33") (pinfunction "AN36_33") (pintype "input"))
    )
    (net (code "98") (name "unconnected-(U1B-AN37-Pad32)") (class "Default")
      (node (ref "U1") (pin "32") (pinfunction "AN37_32") (pintype "input"))
    )
    (net (code "99") (name "unconnected-(U1B-AN38-Pad31)") (class "Default")
      (node (ref "U1") (pin "31") (pinfunction "AN38_31") (pintype "input"))
    )
    (net (code "100") (name "unconnected-(U1B-AN39-Pad30)") (class "Default")
      (node (ref "U1") (pin "30") (pinfunction "AN39_30") (pintype "input"))
    )
    (net (code "101") (name "unconnected-(U1B-AN44-Pad29)") (class "Default")
      (node (ref "U1") (pin "29") (pinfunction "AN44_29") (pintype "input"))
    )
    (net (code "102") (name "unconnected-(U1B-AN45-Pad28)") (class "Default")
      (node (ref "U1") (pin "28") (pinfunction "AN45_28") (pintype "input"))
    )
    (net (code "103") (name "unconnected-(U1B-AN46-Pad27)") (class "Default")
      (node (ref "U1") (pin "27") (pinfunction "AN46_27") (pintype "input"))
    )
    (net (code "104") (name "unconnected-(U1B-AN47-Pad26)") (class "Default")
      (node (ref "U1") (pin "26") (pinfunction "AN47_26") (pintype "input"))
    )
    (net (code "105") (name "unconnected-(U1B-AN48-Pad25)") (class "Default")
      (node (ref "U1") (pin "25") (pinfunction "AN48_25") (pintype "input"))
    )
    (net (code "106") (name "unconnected-(U1B-AN49-Pad24)") (class "Default")
      (node (ref "U1") (pin "24") (pinfunction "AN49_24") (pintype "input"))
    )
    (net (code "107") (name "unconnected-(U1C-P00_8-Pad19)") (class "Default")
      (node (ref "U1") (pin "19") (pinfunction "P00_8_19") (pintype "bidirectional"))
    )
    (net (code "108") (name "unconnected-(U1C-P00_9-Pad20)") (class "Default")
      (node (ref "U1") (pin "20") (pinfunction "P00_9_20") (pintype "bidirectional"))
    )
    (net (code "109") (name "unconnected-(U1C-P00_12-Pad21)") (class "Default")
      (node (ref "U1") (pin "21") (pinfunction "P00_12_21") (pintype "bidirectional"))
    )
    (net (code "110") (name "unconnected-(U1C-P02_4-Pad5)") (class "Default")
      (node (ref "U1") (pin "5") (pinfunction "P02_4_5") (pintype "bidirectional"))
    )
    (net (code "111") (name "unconnected-(U1C-P02_5-Pad6)") (class "Default")
      (node (ref "U1") (pin "6") (pinfunction "P02_5_6") (pintype "bidirectional"))
    )
    (net (code "112") (name "unconnected-(U1C-P02_6-Pad7)") (class "Default")
      (node (ref "U1") (pin "7") (pinfunction "P02_6_7") (pintype "bidirectional"))
    )
    (net (code "113") (name "unconnected-(U1C-P02_7-Pad8)") (class "Default")
      (node (ref "U1") (pin "8") (pinfunction "P02_7_8") (pintype "bidirectional"))
    )
    (net (code "114") (name "unconnected-(U1C-P10_1-Pad140)") (class "Default")
      (node (ref "U1") (pin "140") (pinfunction "P10_1_140") (pintype "bidirectional"))
    )
    (net (code "115") (name "unconnected-(U1C-P10_2-Pad141)") (class "Default")
      (node (ref "U1") (pin "141") (pinfunction "P10_2_141") (pintype "bidirectional"))
    )
    (net (code "116") (name "unconnected-(U1C-P10_3-Pad142)") (class "Default")
      (node (ref "U1") (pin "142") (pinfunction "P10_3_142") (pintype "bidirectional"))
    )
    (net (code "117") (name "unconnected-(U1C-P11_2-Pad132)") (class "Default")
      (node (ref "U1") (pin "132") (pinfunction "P11_2_132") (pintype "bidirectional"))
    )
    (net (code "118") (name "unconnected-(U1C-P11_3-Pad133)") (class "Default")
      (node (ref "U1") (pin "133") (pinfunction "P11_3_133") (pintype "bidirectional"))
    )
    (net (code "119") (name "unconnected-(U1C-P11_10-Pad137)") (class "Default")
      (node (ref "U1") (pin "137") (pinfunction "P11_10_137") (pintype "bidirectional"))
    )
    (net (code "120") (name "unconnected-(U1C-P11_11-Pad138)") (class "Default")
      (node (ref "U1") (pin "138") (pinfunction "P11_11_138") (pintype "bidirectional"))
    )
    (net (code "121") (name "unconnected-(U1C-P11_12-Pad139)") (class "Default")
      (node (ref "U1") (pin "139") (pinfunction "P11_12_139") (pintype "bidirectional"))
    )
    (net (code "122") (name "unconnected-(U1C-P13_0-Pad128)") (class "Default")
      (node (ref "U1") (pin "128") (pinfunction "P13_0_128") (pintype "bidirectional"))
    )
    (net (code "123") (name "unconnected-(U1C-P13_1-Pad129)") (class "Default")
      (node (ref "U1") (pin "129") (pinfunction "P13_1_129") (pintype "bidirectional"))
    )
    (net (code "124") (name "unconnected-(U1C-P13_2-Pad130)") (class "Default")
      (node (ref "U1") (pin "130") (pinfunction "P13_2_130") (pintype "bidirectional"))
    )
    (net (code "125") (name "unconnected-(U1C-P13_3-Pad131)") (class "Default")
      (node (ref "U1") (pin "131") (pinfunction "P13_3_131") (pintype "bidirectional"))
    )
    (net (code "126") (name "unconnected-(U1C-P14_0-Pad118)") (class "Default")
      (node (ref "U1") (pin "118") (pinfunction "P14_0_118") (pintype "bidirectional"))
    )
    (net (code "127") (name "unconnected-(U1C-P14_1-Pad119)") (class "Default")
      (node (ref "U1") (pin "119") (pinfunction "P14_1_119") (pintype "bidirectional"))
    )
    (net (code "128") (name "unconnected-(U1C-P14_2-Pad120)") (class "Default")
      (node (ref "U1") (pin "120") (pinfunction "P14_2_120") (pintype "bidirectional"))
    )
    (net (code "129") (name "unconnected-(U1C-P14_3-Pad121)") (class "Default")
      (node (ref "U1") (pin "121") (pinfunction "P14_3_121") (pintype "bidirectional"))
    )
    (net (code "130") (name "unconnected-(U1C-P14_6-Pad124)") (class "Default")
      (node (ref "U1") (pin "124") (pinfunction "P14_6_124") (pintype "bidirectional"))
    )
    (net (code "131") (name "unconnected-(U1D-P15_4-Pad113)") (class "Default")
      (node (ref "U1") (pin "113") (pinfunction "P15_4_113") (pintype "bidirectional"))
    )
    (net (code "132") (name "unconnected-(U1D-P15_6-Pad115)") (class "Default")
      (node (ref "U1") (pin "115") (pinfunction "P15_6_115") (pintype "bidirectional"))
    )
    (net (code "133") (name "unconnected-(U1D-P15_7-Pad116)") (class "Default")
      (node (ref "U1") (pin "116") (pinfunction "P15_7_116") (pintype "bidirectional"))
    )
    (net (code "134") (name "unconnected-(U1D-P15_8-Pad117)") (class "Default")
      (node (ref "U1") (pin "117") (pinfunction "P15_8_117") (pintype "bidirectional"))
    )
    (net (code "135") (name "unconnected-(U1D-P20_0-Pad93)") (class "Default")
      (node (ref "U1") (pin "93") (pinfunction "P20_0_93") (pintype "bidirectional"))
    )
    (net (code "136") (name "unconnected-(U1D-P20_3-Pad95)") (class "Default")
      (node (ref "U1") (pin "95") (pinfunction "P20_3_95") (pintype "bidirectional"))
    )
    (net (code "137") (name "unconnected-(U1D-P20_10-Pad104)") (class "Default")
      (node (ref "U1") (pin "104") (pinfunction "P20_10_104") (pintype "bidirectional"))
    )
    (net (code "138") (name "unconnected-(U1D-P21_2-Pad84)") (class "Default")
      (node (ref "U1") (pin "84") (pinfunction "P21_2_84") (pintype "bidirectional"))
    )
    (net (code "139") (name "unconnected-(U1D-P21_3-Pad85)") (class "Default")
      (node (ref "U1") (pin "85") (pinfunction "P21_3_85") (pintype "bidirectional"))
    )
    (net (code "140") (name "unconnected-(U1D-P21_4-Pad86)") (class "Default")
      (node (ref "U1") (pin "86") (pinfunction "P21_4_86") (pintype "bidirectional"))
    )
    (net (code "141") (name "unconnected-(U1D-P21_5-Pad87)") (class "Default")
      (node (ref "U1") (pin "87") (pinfunction "P21_5_87") (pintype "bidirectional"))
    )
    (net (code "142") (name "unconnected-(U1D-P21_6{slash}TDI-Pad88)") (class "Default")
      (node (ref "U1") (pin "88") (pinfunction "P21_6/TDI_88") (pintype "bidirectional"))
    )
    (net (code "143") (name "unconnected-(U1D-P22_3-Pad77)") (class "Default")
      (node (ref "U1") (pin "77") (pinfunction "P22_3_77") (pintype "bidirectional"))
    )
    (net (code "144") (name "unconnected-(U1D-P23_1-Pad73)") (class "Default")
      (node (ref "U1") (pin "73") (pinfunction "P23_1_73") (pintype "bidirectional"))
    )
    (net (code "145") (name "unconnected-(U1D-P32_0{slash}VGATE1N-Pad70)") (class "Default")
      (node (ref "U1") (pin "70") (pinfunction "P32_0/VGATE1N_70") (pintype "bidirectional"))
    )
    (net (code "146") (name "unconnected-(U1D-P32_4-Pad72)") (class "Default")
      (node (ref "U1") (pin "72") (pinfunction "P32_4_72") (pintype "bidirectional"))
    )
    (net (code "147") (name "unconnected-(U1D-P33_4-Pad60)") (class "Default")
      (node (ref "U1") (pin "60") (pinfunction "P33_4_60") (pintype "bidirectional"))
    )
    (net (code "148") (name "unconnected-(U1D-P33_5-Pad61)") (class "Default")
      (node (ref "U1") (pin "61") (pinfunction "P33_5_61") (pintype "bidirectional"))
    )
    (net (code "149") (name "unconnected-(U1D-P33_8-Pad64)") (class "Default")
      (node (ref "U1") (pin "64") (pinfunction "P33_8_64") (pintype "bidirectional"))
    )
    (net (code "150") (name "unconnected-(U1D-P33_9-Pad65)") (class "Default")
      (node (ref "U1") (pin "65") (pinfunction "P33_9_65") (pintype "bidirectional"))
    )
    (net (code "151") (name "unconnected-(U1D-P33_10-Pad66)") (class "Default")
      (node (ref "U1") (pin "66") (pinfunction "P33_10_66") (pintype "bidirectional"))
    )
    (net (code "152") (name "unconnected-(U1D-P33_11-Pad67)") (class "Default")
      (node (ref "U1") (pin "67") (pinfunction "P33_11_67") (pintype "bidirectional"))
    )
    (net (code "153") (name "unconnected-(U1D-P33_12-Pad68)") (class "Default")
      (node (ref "U1") (pin "68") (pinfunction "P33_12_68") (pintype "bidirectional"))
    )
    (net (code "154") (name "unconnected-(U1D-P33_13-Pad69)") (class "Default")
      (node (ref "U1") (pin "69") (pinfunction "P33_13_69") (pintype "bidirectional"))
    )
    (net (code "155") (name "unconnected-(总钻风-Pad5)") (class "Default")
      (node (ref "总钻风") (pin "5") (pinfunction "5_5") (pintype "passive+no_connect"))
    )
    (net (code "156") (name "unconnected-(总钻风-Pad19)") (class "Default")
      (node (ref "总钻风") (pin "19") (pinfunction "19_19") (pintype "passive+no_connect"))
    )
    (net (code "157") (name "unconnected-(总钻风-Pad20)") (class "Default")
      (node (ref "总钻风") (pin "20") (pinfunction "20_20") (pintype "passive+no_connect"))
    )
  )
)
